# io.net
KiCad netlist of a schematic drawn in Altium Designer
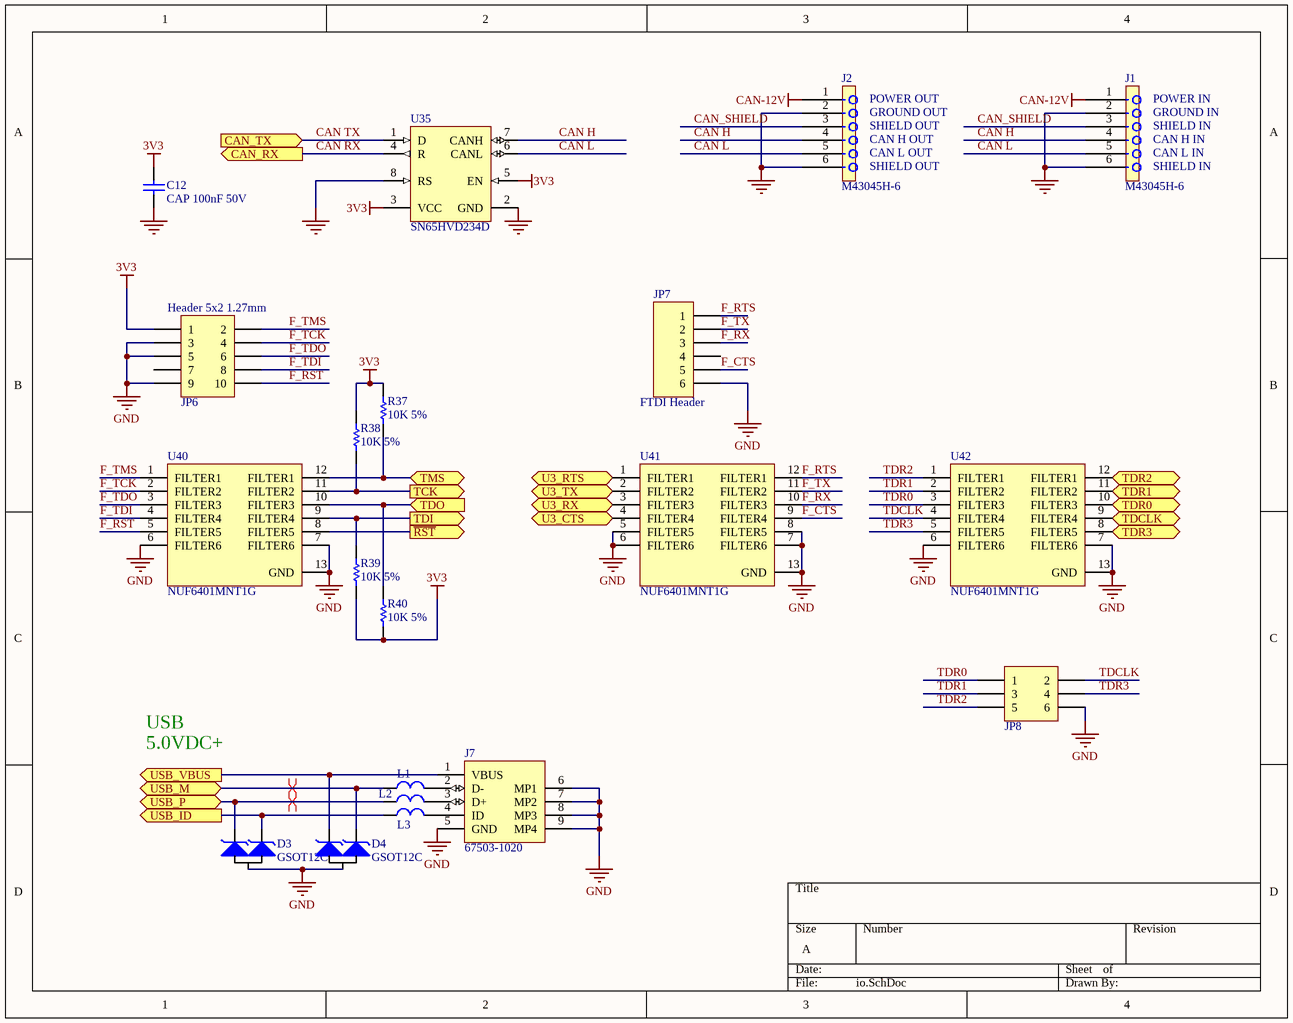
[diagram p0: io.SchDoc]

(export (version "E")
  (design (tool "Eeschema 10.0.6"))
  (components
    (comp (ref "C12")
      (value "CAP 100nF 50V")
      (footprint "CAPC0603(1608)100_M")
      (description "CAP 100nF 50V Â±0.1pF 0603 (1608 Metric) Thickness 1mm SMD")
      (fields (field (name "TOLERANCE") "Â±0.1pF"))
      (libsource (lib "Altium Content Vault") (part "CMP-1035-00010-1"))
    )
    (comp (ref "D3")
      (value "GSOT12C")
      (footprint "SOT-23 - ESD")
      (description "DIO GSOT12C ESD 2LINE 12V SOT23")
      (fields (field (name "MPN") "GSOT12C-E3-08"))
      (libsource (lib "HSBNE-Vend") (part "2749"))
    )
    (comp (ref "D4")
      (value "GSOT12C")
      (footprint "SOT-23 - ESD")
      (description "DIO GSOT12C ESD 2LINE 12V SOT23")
      (fields (field (name "MPN") "GSOT12C-E3-08"))
      (libsource (lib "HSBNE-Vend") (part "2749"))
    )
    (comp (ref "J1") (value "M43045H-6") (footprint "M43045H-6") (libsource (lib "HSBNE-Vend") (part "CON6")))
    (comp (ref "J2") (value "M43045H-6") (footprint "M43045H-6") (libsource (lib "HSBNE-Vend") (part "CON6")))
    (comp (ref "J7")
      (value "67503-1020")
      (footprint "MOLX-67503-1020_V")
      (description "USB, MINI, SMD, RA KME04-USBMU03A01")
      (fields (field (name "MANUFACTURER") "Molex"))
      (libsource (lib "Altium Content Vault") (part "MOLX-67503-1020"))
    )
    (comp (ref "JP6")
      (value "Header 5x2 1.27mm")
      (footprint "SOP10")
      (description "Program")
      (libsource (lib "HSBNE-Vend") (part "Header 5x2"))
    )
    (comp (ref "JP7")
      (value "FTDI Header")
      (footprint "1X6")
      (description "Header, 6-Pin")
      (libsource (lib "snarc+3") (part "Header 6"))
    )
    (comp (ref "JP8")
      (value "Header 3x2 2.54mm")
      (footprint "2X3")
      (description "Header, 6-Pin")
      (libsource (lib "HSBNE-Vend") (part "Header 3x2"))
    )
    (comp (ref "L1")
      (value "MPZ1608S102A")
      (footprint "0603")
      (description "IND FERRITE CHIP BEAD 1000 OHM @ 100MHz 800mA 0603")
      (libsource (lib "LXPN") (part "2982"))
    )
    (comp (ref "L2")
      (value "MPZ1608S102A")
      (footprint "0603")
      (description "IND FERRITE CHIP BEAD 1000 OHM @ 100MHz 800mA 0603")
      (libsource (lib "LXPN") (part "2982"))
    )
    (comp (ref "L3")
      (value "MPZ1608S102A")
      (footprint "0603")
      (description "IND FERRITE CHIP BEAD 1000 OHM @ 100MHz 800mA 0603")
      (libsource (lib "LXPN") (part "2982"))
    )
    (comp (ref "R37")
      (value "10K 5%")
      (footprint "RESC0603(1608)_N")
      (description "10K 0.1W 5% 0603 (1608 Metric)  SMD")
      (fields (field (name "TOLERANCE") "5 %") (field (name "POWER") "0.1 W"))
      (libsource (lib "Altium Content Vault") (part "RES"))
    )
    (comp (ref "R38")
      (value "10K 5%")
      (footprint "RESC0603(1608)_N")
      (description "10K 0.1W 5% 0603 (1608 Metric)  SMD")
      (fields (field (name "TOLERANCE") "5 %") (field (name "POWER") "0.1 W"))
      (libsource (lib "Altium Content Vault") (part "RES"))
    )
    (comp (ref "R39")
      (value "10K 5%")
      (footprint "RESC0603(1608)_N")
      (description "10K 0.1W 5% 0603 (1608 Metric)  SMD")
      (fields (field (name "TOLERANCE") "5 %") (field (name "POWER") "0.1 W"))
      (libsource (lib "Altium Content Vault") (part "RES"))
    )
    (comp (ref "R40")
      (value "10K 5%")
      (footprint "RESC0603(1608)_N")
      (description "10K 0.1W 5% 0603 (1608 Metric)  SMD")
      (fields (field (name "TOLERANCE") "5 %") (field (name "POWER") "0.1 W"))
      (libsource (lib "Altium Content Vault") (part "RES"))
    )
    (comp (ref "U35")
      (value "SN65HVD234D")
      (footprint "D8_M")
      (fields (field (name "MANUFACTURER") "Texas Instruments"))
      (libsource (lib "Altium Content Vault") (part "TI-SN65HVD234-SOIC_D-8"))
    )
    (comp (ref "U40")
      (value "NUF6401MNT1G")
      (footprint "ONSC-DFN-12-506AD-01_V")
      (fields (field (name "MANUFACTURER") "On Semiconductor"))
      (libsource (lib "HSBNE-Vend") (part "CMP-1066-00005-1"))
    )
    (comp (ref "U41")
      (value "NUF6401MNT1G")
      (footprint "ONSC-DFN-12-506AD-01_V")
      (fields (field (name "MANUFACTURER") "On Semiconductor"))
      (libsource (lib "HSBNE-Vend") (part "CMP-1066-00005-1"))
    )
    (comp (ref "U42")
      (value "NUF6401MNT1G")
      (footprint "ONSC-DFN-12-506AD-01_V")
      (fields (field (name "MANUFACTURER") "On Semiconductor"))
      (libsource (lib "HSBNE-Vend") (part "CMP-1066-00005-1"))
    )
  )
  (nets
    (net (code "1") (name "/CAN H") (class "Default")
      (node (ref "J1") (pin "4") (pintype "passive"))
      (node (ref "J2") (pin "4") (pintype "passive"))
      (node (ref "U35") (pin "7") (pinfunction "CANH_7") (pintype "bidirectional"))
    )
    (net (code "2") (name "/CAN L") (class "Default")
      (node (ref "J1") (pin "5") (pintype "passive"))
      (node (ref "J2") (pin "5") (pintype "passive"))
      (node (ref "U35") (pin "6") (pinfunction "CANL_6") (pintype "bidirectional"))
    )
    (net (code "3") (name "/CAN RX") (class "Default")
      (node (ref "U35") (pin "4") (pinfunction "R_4") (pintype "output"))
    )
    (net (code "4") (name "/CAN TX") (class "Default")
      (node (ref "U35") (pin "1") (pinfunction "D_1") (pintype "input"))
    )
    (net (code "5") (name "/CAN_SHIELD") (class "Default")
      (node (ref "J1") (pin "3") (pintype "passive"))
      (node (ref "J2") (pin "3") (pintype "passive"))
    )
    (net (code "6") (name "/F_CTS") (class "Default")
      (node (ref "JP7") (pin "5") (pinfunction "5_5") (pintype "passive"))
      (node (ref "U41") (pin "9") (pinfunction "FILTER4_9") (pintype "passive"))
    )
    (net (code "7") (name "/F_RTS") (class "Default")
      (node (ref "JP7") (pin "1") (pinfunction "1_1") (pintype "passive"))
      (node (ref "U41") (pin "12") (pinfunction "FILTER1_12") (pintype "passive"))
    )
    (net (code "8") (name "/F_RX") (class "Default")
      (node (ref "JP7") (pin "3") (pinfunction "3_3") (pintype "passive"))
      (node (ref "U41") (pin "10") (pinfunction "FILTER3_10") (pintype "passive"))
    )
    (net (code "9") (name "/F_TCK") (class "Default")
      (node (ref "JP6") (pin "4") (pinfunction "4_4") (pintype "passive"))
      (node (ref "U40") (pin "2") (pinfunction "FILTER2_2") (pintype "passive"))
    )
    (net (code "10") (name "/F_TDI") (class "Default")
      (node (ref "JP6") (pin "8") (pinfunction "8_8") (pintype "passive"))
      (node (ref "U40") (pin "4") (pinfunction "FILTER4_4") (pintype "passive"))
    )
    (net (code "11") (name "/F_TDO") (class "Default")
      (node (ref "JP6") (pin "6") (pinfunction "6_6") (pintype "passive"))
      (node (ref "U40") (pin "3") (pinfunction "FILTER3_3") (pintype "passive"))
    )
    (net (code "12") (name "/F_TMS") (class "Default")
      (node (ref "JP6") (pin "2") (pinfunction "2_2") (pintype "passive"))
      (node (ref "U40") (pin "1") (pinfunction "FILTER1_1") (pintype "passive"))
    )
    (net (code "13") (name "/F_TX") (class "Default")
      (node (ref "JP7") (pin "2") (pinfunction "2_2") (pintype "passive"))
      (node (ref "U41") (pin "11") (pinfunction "FILTER2_11") (pintype "passive"))
    )
    (net (code "14") (name "/F_~{RST}") (class "Default")
      (node (ref "JP6") (pin "10") (pinfunction "10_10") (pintype "passive"))
      (node (ref "U40") (pin "5") (pinfunction "FILTER5_5") (pintype "passive"))
    )
    (net (code "15") (name "/TCK") (class "Default")
      (node (ref "R38") (pin "1") (pinfunction "1_1") (pintype "passive"))
      (node (ref "U40") (pin "11") (pinfunction "FILTER2_11") (pintype "passive"))
    )
    (net (code "16") (name "/TDCLK") (class "Default")
      (node (ref "JP8") (pin "2") (pinfunction "2_2") (pintype "passive"))
      (node (ref "U42") (pin "4") (pinfunction "FILTER4_4") (pintype "passive"))
    )
    (net (code "17") (name "/TDI") (class "Default")
      (node (ref "R39") (pin "2") (pinfunction "2_2") (pintype "passive"))
      (node (ref "U40") (pin "9") (pinfunction "FILTER4_9") (pintype "passive"))
    )
    (net (code "18") (name "/TDO") (class "Default")
      (node (ref "R40") (pin "2") (pinfunction "2_2") (pintype "passive"))
      (node (ref "U40") (pin "10") (pinfunction "FILTER3_10") (pintype "passive"))
    )
    (net (code "19") (name "/TDR0") (class "Default")
      (node (ref "JP8") (pin "1") (pinfunction "1_1") (pintype "passive"))
      (node (ref "U42") (pin "3") (pinfunction "FILTER3_3") (pintype "passive"))
    )
    (net (code "20") (name "/TDR1") (class "Default")
      (node (ref "JP8") (pin "3") (pinfunction "3_3") (pintype "passive"))
      (node (ref "U42") (pin "2") (pinfunction "FILTER2_2") (pintype "passive"))
    )
    (net (code "21") (name "/TDR2") (class "Default")
      (node (ref "JP8") (pin "5") (pinfunction "5_5") (pintype "passive"))
      (node (ref "U42") (pin "1") (pinfunction "FILTER1_1") (pintype "passive"))
    )
    (net (code "22") (name "/TDR3") (class "Default")
      (node (ref "JP8") (pin "4") (pinfunction "4_4") (pintype "passive"))
      (node (ref "U42") (pin "5") (pinfunction "FILTER5_5") (pintype "passive"))
    )
    (net (code "23") (name "/TMS") (class "Default")
      (node (ref "R37") (pin "1") (pinfunction "1_1") (pintype "passive"))
      (node (ref "U40") (pin "12") (pinfunction "FILTER1_12") (pintype "passive"))
    )
    (net (code "24") (name "/U3_CTS") (class "Default")
      (node (ref "U41") (pin "4") (pinfunction "FILTER4_4") (pintype "passive"))
    )
    (net (code "25") (name "/U3_RTS") (class "Default")
      (node (ref "U41") (pin "1") (pinfunction "FILTER1_1") (pintype "passive"))
    )
    (net (code "26") (name "/U3_RX") (class "Default")
      (node (ref "U41") (pin "3") (pinfunction "FILTER3_3") (pintype "passive"))
    )
    (net (code "27") (name "/U3_TX") (class "Default")
      (node (ref "U41") (pin "2") (pinfunction "FILTER2_2") (pintype "passive"))
    )
    (net (code "28") (name "/USB_ID") (class "Default")
      (node (ref "D3") (pin "2") (pinfunction "K2_2") (pintype "passive"))
      (node (ref "L3") (pin "1") (pinfunction "1_1") (pintype "passive"))
    )
    (net (code "29") (name "/USB_M") (class "Default")
      (node (ref "D4") (pin "2") (pinfunction "K2_2") (pintype "passive"))
      (node (ref "L1") (pin "1") (pinfunction "1_1") (pintype "passive"))
    )
    (net (code "30") (name "/USB_P") (class "Default")
      (node (ref "D3") (pin "1") (pinfunction "K1_1") (pintype "passive"))
      (node (ref "L2") (pin "1") (pinfunction "1_1") (pintype "passive"))
    )
    (net (code "31") (name "/USB_VBUS") (class "Default")
      (node (ref "D4") (pin "1") (pinfunction "K1_1") (pintype "passive"))
      (node (ref "J7") (pin "1") (pinfunction "VBUS_1") (pintype "power_in"))
    )
    (net (code "32") (name "/~{RST}") (class "Default")
      (node (ref "U40") (pin "8") (pinfunction "FILTER5_8") (pintype "passive"))
    )
    (net (code "33") (name "3V3") (class "Default")
      (node (ref "C12") (pin "2") (pinfunction "2_2") (pintype "passive"))
      (node (ref "JP6") (pin "1") (pinfunction "1_1") (pintype "passive"))
      (node (ref "R37") (pin "2") (pinfunction "2_2") (pintype "passive"))
      (node (ref "R38") (pin "2") (pinfunction "2_2") (pintype "passive"))
      (node (ref "R39") (pin "1") (pinfunction "1_1") (pintype "passive"))
      (node (ref "R40") (pin "1") (pinfunction "1_1") (pintype "passive"))
      (node (ref "U35") (pin "3") (pinfunction "VCC_3") (pintype "power_in"))
      (node (ref "U35") (pin "5") (pinfunction "EN_5") (pintype "input"))
    )
    (net (code "34") (name "CAN-12V") (class "Default")
      (node (ref "J1") (pin "1") (pintype "passive"))
      (node (ref "J2") (pin "1") (pintype "passive"))
    )
    (net (code "35") (name "GND") (class "Default")
      (node (ref "C12") (pin "1") (pinfunction "1_1") (pintype "passive"))
      (node (ref "D3") (pin "3") (pinfunction "A_3") (pintype "passive"))
      (node (ref "D4") (pin "3") (pinfunction "A_3") (pintype "passive"))
      (node (ref "J1") (pin "2") (pintype "passive"))
      (node (ref "J1") (pin "6") (pintype "passive"))
      (node (ref "J2") (pin "2") (pintype "passive"))
      (node (ref "J2") (pin "6") (pintype "passive"))
      (node (ref "J7") (pin "5") (pinfunction "GND_5") (pintype "power_in"))
      (node (ref "J7") (pin "6") (pinfunction "MP1_6") (pintype "passive"))
      (node (ref "J7") (pin "7") (pinfunction "MP2_7") (pintype "passive"))
      (node (ref "J7") (pin "8") (pinfunction "MP3_8") (pintype "passive"))
      (node (ref "J7") (pin "9") (pinfunction "MP4_9") (pintype "passive"))
      (node (ref "JP6") (pin "3") (pinfunction "3_3") (pintype "passive"))
      (node (ref "JP6") (pin "5") (pinfunction "5_5") (pintype "passive"))
      (node (ref "JP6") (pin "9") (pinfunction "9_9") (pintype "passive"))
      (node (ref "JP7") (pin "6") (pinfunction "6_6") (pintype "passive"))
      (node (ref "JP8") (pin "6") (pinfunction "6_6") (pintype "passive"))
      (node (ref "U35") (pin "2") (pinfunction "GND_2") (pintype "power_in"))
      (node (ref "U35") (pin "8") (pinfunction "RS_8") (pintype "input"))
      (node (ref "U40") (pin "13") (pinfunction "GND_13") (pintype "power_in"))
      (node (ref "U40") (pin "6") (pinfunction "FILTER6_6") (pintype "passive"))
      (node (ref "U40") (pin "7") (pinfunction "FILTER6_7") (pintype "passive"))
      (node (ref "U41") (pin "13") (pinfunction "GND_13") (pintype "power_in"))
      (node (ref "U41") (pin "5") (pinfunction "FILTER5_5") (pintype "passive"))
      (node (ref "U41") (pin "6") (pinfunction "FILTER6_6") (pintype "passive"))
      (node (ref "U41") (pin "7") (pinfunction "FILTER6_7") (pintype "passive"))
      (node (ref "U41") (pin "8") (pinfunction "FILTER5_8") (pintype "passive"))
      (node (ref "U42") (pin "13") (pinfunction "GND_13") (pintype "power_in"))
      (node (ref "U42") (pin "6") (pinfunction "FILTER6_6") (pintype "passive"))
      (node (ref "U42") (pin "7") (pinfunction "FILTER6_7") (pintype "passive"))
    )
    (net (code "36") (name "Net-(J7-D+)") (class "Default")
      (node (ref "J7") (pin "3") (pinfunction "D+_3") (pintype "bidirectional"))
      (node (ref "L2") (pin "2") (pinfunction "2_2") (pintype "passive"))
    )
    (net (code "37") (name "Net-(J7-D-)") (class "Default")
      (node (ref "J7") (pin "2") (pinfunction "D-_2") (pintype "bidirectional"))
      (node (ref "L1") (pin "2") (pinfunction "2_2") (pintype "passive"))
    )
    (net (code "38") (name "Net-(J7-ID)") (class "Default")
      (node (ref "J7") (pin "4") (pinfunction "ID_4") (pintype "passive"))
      (node (ref "L3") (pin "2") (pinfunction "2_2") (pintype "passive"))
    )
    (net (code "39") (name "unconnected-(JP6-Pad7)") (class "Default")
      (node (ref "JP6") (pin "7") (pinfunction "7_7") (pintype "passive"))
    )
    (net (code "40") (name "unconnected-(JP7-Pad4)") (class "Default")
      (node (ref "JP7") (pin "4") (pinfunction "4_4") (pintype "passive"))
    )
    (net (code "41") (name "unconnected-(U42-FILTER1-Pad12)") (class "Default")
      (node (ref "U42") (pin "12") (pinfunction "FILTER1_12") (pintype "passive"))
    )
    (net (code "42") (name "unconnected-(U42-FILTER2-Pad11)") (class "Default")
      (node (ref "U42") (pin "11") (pinfunction "FILTER2_11") (pintype "passive"))
    )
    (net (code "43") (name "unconnected-(U42-FILTER3-Pad10)") (class "Default")
      (node (ref "U42") (pin "10") (pinfunction "FILTER3_10") (pintype "passive"))
    )
    (net (code "44") (name "unconnected-(U42-FILTER4-Pad9)") (class "Default")
      (node (ref "U42") (pin "9") (pinfunction "FILTER4_9") (pintype "passive"))
    )
    (net (code "45") (name "unconnected-(U42-FILTER5-Pad8)") (class "Default")
      (node (ref "U42") (pin "8") (pinfunction "FILTER5_8") (pintype "passive"))
    )
  )
)
